# OpenThermEth.net
KiCad netlist of a schematic drawn in EasyEDA Pro
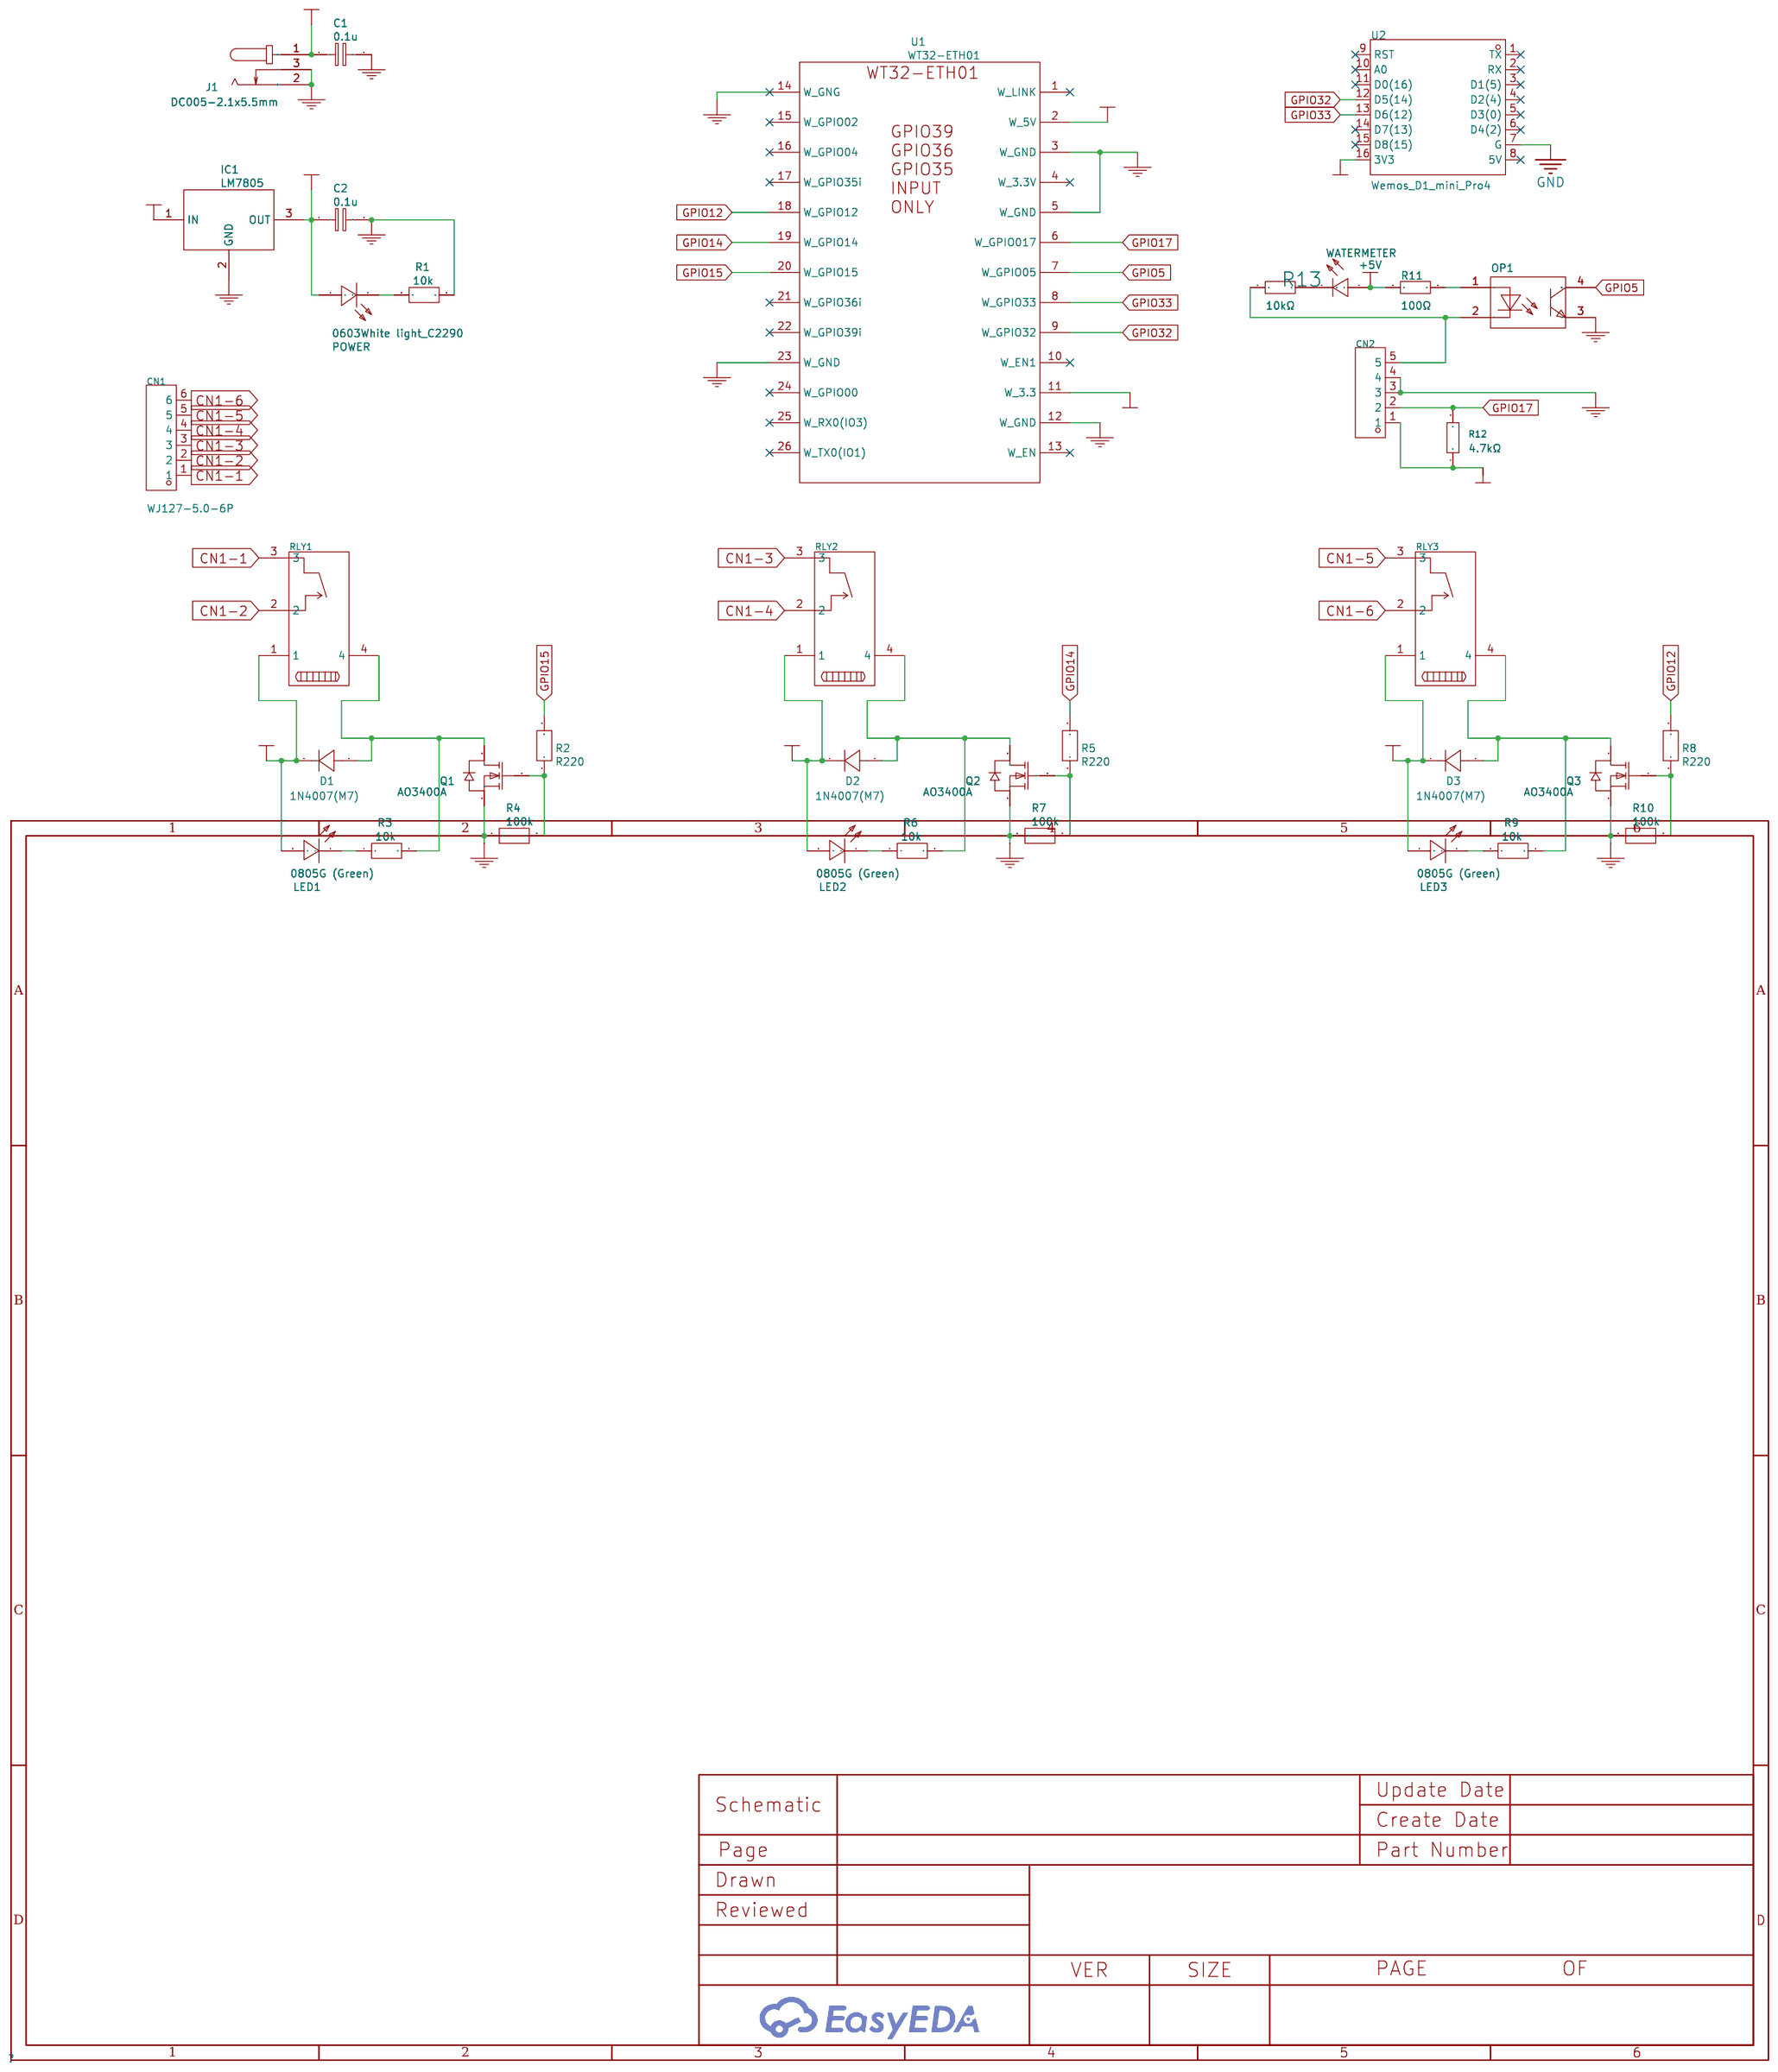
[diagram p0: schematic sheet]

(export (version "E")
  (design (tool "Eeschema 10.0.6"))
  (components
    (comp (ref "C1")
      (value "0.1u")
      (footprint "easyedapro:C0603")
      (fields
        (field (name "Manufacturer Part") "CL05B104KO5NNNC")
        (field (name "Manufacturer") "SAMSUNG(三星)")
      )
      (libsource (lib "easyedapro") (part "0.1u"))
    )
    (comp (ref "C2")
      (value "0.1u")
      (footprint "easyedapro:C0603")
      (fields
        (field (name "Manufacturer Part") "CL05B104KO5NNNC")
        (field (name "Manufacturer") "SAMSUNG(三星)")
      )
      (libsource (lib "easyedapro") (part "0.1u"))
    )
    (comp (ref "CN1")
      (value "WJ127-5.0-6P")
      (footprint "easyedapro:CONN-TH_6P-P5.00_WJ127-5.0-6P")
      (fields (field (name "Manufacturer") "KANGNEX(康奈克斯电气)"))
      (libsource (lib "easyedapro") (part "WJ127-5.0-6P"))
    )
    (comp (ref "CN2")
      (value "WJ127-5.0-5P")
      (footprint "easyedapro:CONN-TH_5P-P5.00_WJ127-5.0-5P")
      (fields (field (name "Manufacturer") "KANGNEX(康奈克斯电气)"))
      (libsource (lib "easyedapro") (part "WJ127-5.0-5P"))
    )
    (comp (ref "D1")
      (value "1N4007(M7)")
      (footprint "easyedapro:SMA_L4.3-W2.7-LS5.1-RD")
      (fields (field (name "Manufacturer") "UMW(友台半导体)"))
      (libsource (lib "easyedapro") (part "1N4007(M7)"))
    )
    (comp (ref "D2")
      (value "1N4007(M7)")
      (footprint "easyedapro:SMA_L4.3-W2.7-LS5.1-RD")
      (fields (field (name "Manufacturer") "UMW(友台半导体)"))
      (libsource (lib "easyedapro") (part "1N4007(M7)"))
    )
    (comp (ref "D3")
      (value "1N4007(M7)")
      (footprint "easyedapro:SMA_L4.3-W2.7-LS5.1-RD")
      (fields (field (name "Manufacturer") "UMW(友台半导体)"))
      (libsource (lib "easyedapro") (part "1N4007(M7)"))
    )
    (comp (ref "IC1")
      (value "LM7805")
      (footprint "easyedapro:LM7805")
      (libsource (lib "easyedapro") (part "LM7805"))
    )
    (comp (ref "J1")
      (value "DC005-2.1x5.5mm")
      (footprint "easyedapro:DC-IN-TH_POWER-JACK")
      (fields (field (name "Manufacturer Part") "POWER-JACK") (field (name "Manufacturer") "索峰"))
      (libsource (lib "easyedapro") (part "DC005-2.1x5.5mm"))
    )
    (comp (ref "LED1")
      (value "0805G (Green)")
      (footprint "easyedapro:LED0805-RD_GREEN")
      (fields (field (name "Manufacturer") "KENTO"))
      (libsource (lib "easyedapro") (part "0805G (Green)"))
    )
    (comp (ref "LED2")
      (value "0805G (Green)")
      (footprint "easyedapro:LED0805-RD_GREEN")
      (fields (field (name "Manufacturer") "KENTO"))
      (libsource (lib "easyedapro") (part "0805G (Green)"))
    )
    (comp (ref "LED3")
      (value "0805G (Green)")
      (footprint "easyedapro:LED0805-RD_GREEN")
      (fields (field (name "Manufacturer") "KENTO"))
      (libsource (lib "easyedapro") (part "0805G (Green)"))
    )
    (comp (ref "OP1")
      (value "EL817S1(C)(TU)-F")
      (footprint "easyedapro:OPTO-SMD-4_L4.6-W6.5-P2.54-LS10.3-TL")
      (fields (field (name "Manufacturer") "EVERLIGHT(亿光)"))
      (libsource (lib "easyedapro") (part "EL817S1(C)(TU)-F"))
    )
    (comp (ref "POWER")
      (value "0603White light_C2290")
      (footprint "easyedapro:LED0603-R-RD_WHITE")
      (fields (field (name "Manufacturer Part") "KT-0603W") (field (name "Manufacturer") "KENTO"))
      (libsource (lib "easyedapro") (part "0603White light_C2290"))
    )
    (comp (ref "Q1")
      (value "AO3400A")
      (footprint "easyedapro:SOT-23-3_L2.9-W1.6-P1.90-LS2.8-BR")
      (fields (field (name "Manufacturer") "AOS"))
      (libsource (lib "easyedapro") (part "AO3400A"))
    )
    (comp (ref "Q2")
      (value "AO3400A")
      (footprint "easyedapro:SOT-23-3_L2.9-W1.6-P1.90-LS2.8-BR")
      (fields (field (name "Manufacturer") "AOS"))
      (libsource (lib "easyedapro") (part "AO3400A"))
    )
    (comp (ref "Q3")
      (value "AO3400A")
      (footprint "easyedapro:SOT-23-3_L2.9-W1.6-P1.90-LS2.8-BR")
      (fields (field (name "Manufacturer") "AOS"))
      (libsource (lib "easyedapro") (part "AO3400A"))
    )
    (comp (ref "R1")
      (value "10k")
      (footprint "easyedapro:R0603")
      (fields
        (field (name "Manufacturer Part") "0603WAF1002T5E")
        (field (name "Manufacturer") "UNI-ROYAL(厚声)")
      )
      (libsource (lib "easyedapro") (part "10k"))
    )
    (comp (ref "R2")
      (value "R220")
      (footprint "easyedapro:R0603")
      (fields
        (field (name "Manufacturer Part") "0603WAF2200T5E")
        (field (name "Manufacturer") "UNI-ROYAL(厚声)")
      )
      (libsource (lib "easyedapro") (part "R220"))
    )
    (comp (ref "R3")
      (value "10k")
      (footprint "easyedapro:R0603")
      (fields
        (field (name "Manufacturer Part") "0603WAF1002T5E")
        (field (name "Manufacturer") "UNI-ROYAL(厚声)")
      )
      (libsource (lib "easyedapro") (part "10k"))
    )
    (comp (ref "R4")
      (value "100k")
      (footprint "easyedapro:R0603")
      (fields
        (field (name "Manufacturer Part") "0603WAF1003T5E")
        (field (name "Manufacturer") "UNI-ROYAL(厚声)")
      )
      (libsource (lib "easyedapro") (part "100k"))
    )
    (comp (ref "R5")
      (value "R220")
      (footprint "easyedapro:R0603")
      (fields
        (field (name "Manufacturer Part") "0603WAF2200T5E")
        (field (name "Manufacturer") "UNI-ROYAL(厚声)")
      )
      (libsource (lib "easyedapro") (part "R220"))
    )
    (comp (ref "R6")
      (value "10k")
      (footprint "easyedapro:R0603")
      (fields
        (field (name "Manufacturer Part") "0603WAF1002T5E")
        (field (name "Manufacturer") "UNI-ROYAL(厚声)")
      )
      (libsource (lib "easyedapro") (part "10k"))
    )
    (comp (ref "R7")
      (value "100k")
      (footprint "easyedapro:R0603")
      (fields
        (field (name "Manufacturer Part") "0603WAF1003T5E")
        (field (name "Manufacturer") "UNI-ROYAL(厚声)")
      )
      (libsource (lib "easyedapro") (part "100k"))
    )
    (comp (ref "R8")
      (value "R220")
      (footprint "easyedapro:R0603")
      (fields
        (field (name "Manufacturer Part") "0603WAF2200T5E")
        (field (name "Manufacturer") "UNI-ROYAL(厚声)")
      )
      (libsource (lib "easyedapro") (part "R220"))
    )
    (comp (ref "R9")
      (value "10k")
      (footprint "easyedapro:R0603")
      (fields
        (field (name "Manufacturer Part") "0603WAF1002T5E")
        (field (name "Manufacturer") "UNI-ROYAL(厚声)")
      )
      (libsource (lib "easyedapro") (part "10k"))
    )
    (comp (ref "R10")
      (value "100k")
      (footprint "easyedapro:R0603")
      (fields
        (field (name "Manufacturer Part") "0603WAF1003T5E")
        (field (name "Manufacturer") "UNI-ROYAL(厚声)")
      )
      (libsource (lib "easyedapro") (part "100k"))
    )
    (comp (ref "R11")
      (value "100Ω")
      (footprint "easyedapro:R0805")
      (fields
        (field (name "Manufacturer Part") "0805W8F1000T5E")
        (field (name "Manufacturer") "UNI-ROYAL(厚声)")
      )
      (libsource (lib "easyedapro") (part "0805W8F1000T5E"))
    )
    (comp (ref "R12")
      (value "4.7kΩ")
      (footprint "easyedapro:R0805")
      (fields
        (field (name "Manufacturer Part") "0805W8F4701T5E")
        (field (name "Manufacturer") "UNI-ROYAL(厚声)")
      )
      (libsource (lib "easyedapro") (part "0805W8F4701T5E"))
    )
    (comp (ref "R13")
      (value "10kΩ")
      (footprint "easyedapro:R0603")
      (fields
        (field (name "Manufacturer Part") "0603WAF1002T5E")
        (field (name "Manufacturer") "UNI-ROYAL(厚声)")
      )
      (libsource (lib "easyedapro") (part "0603WAF1002T5E"))
    )
    (comp (ref "RLY1")
      (value "G5NB-1A-E-DC5V")
      (footprint "easyedapro:RELAY-TH_G5NB-1A-E-DCXX")
      (fields (field (name "Manufacturer") "OMRON(欧姆龙)"))
      (libsource (lib "easyedapro") (part "G5NB-1A-E-DC5V"))
    )
    (comp (ref "RLY2")
      (value "G5NB-1A-E-DC5V")
      (footprint "easyedapro:RELAY-TH_G5NB-1A-E-DCXX")
      (fields (field (name "Manufacturer") "OMRON(欧姆龙)"))
      (libsource (lib "easyedapro") (part "G5NB-1A-E-DC5V"))
    )
    (comp (ref "RLY3")
      (value "G5NB-1A-E-DC5V")
      (footprint "easyedapro:RELAY-TH_G5NB-1A-E-DCXX")
      (fields (field (name "Manufacturer") "OMRON(欧姆龙)"))
      (libsource (lib "easyedapro") (part "G5NB-1A-E-DC5V"))
    )
    (comp (ref "U1")
      (value "WT32-ETH01")
      (footprint "easyedapro:WT32-ETH01-M")
      (fields (field (name "Manufacturer") "Wireless-Tag"))
      (libsource (lib "easyedapro") (part "WT32-ETH01"))
    )
    (comp (ref "U2")
      (value "Wemos_D1_mini_Pro4")
      (footprint "easyedapro:DIP-16_WEMOS_D1_MINI_PRO4")
      (libsource (lib "easyedapro") (part "WEMOS_D1_MINI_PRO4"))
    )
    (comp (ref "WATERMETER")
      (value "19-213/Y2C-CQ2R2L/3T(CY)")
      (footprint "easyedapro:LED0603-RD-YELLOW")
      (fields (field (name "Manufacturer") "EVERLIGHT(亿光)"))
      (libsource (lib "easyedapro") (part "19-213/Y2C-CQ2R2L/3T(CY)"))
    )
  )
  (nets
    (net (code "1") (name "+3.3V") (class "Default")
      (node (ref "CN2") (pin "1") (pinfunction "1_1") (pintype "input"))
      (node (ref "R12") (pin "1") (pinfunction "1_1") (pintype "input"))
      (node (ref "U1") (pin "11") (pinfunction "W_3.3_11") (pintype "unspecified"))
      (node (ref "U2") (pin "16") (pinfunction "3V3_16") (pintype "unspecified"))
    )
    (net (code "2") (name "+5V") (class "Default")
      (node (ref "C2") (pin "1") (pinfunction "1_1") (pintype "unspecified"))
      (node (ref "D1") (pin "1") (pinfunction "K_1") (pintype "unspecified"))
      (node (ref "D2") (pin "1") (pinfunction "K_1") (pintype "unspecified"))
      (node (ref "D3") (pin "1") (pinfunction "K_1") (pintype "unspecified"))
      (node (ref "IC1") (pin "3") (pinfunction "OUT_3") (pintype "unspecified"))
      (node (ref "LED1") (pin "2") (pinfunction "A_2") (pintype "unspecified"))
      (node (ref "LED2") (pin "2") (pinfunction "A_2") (pintype "unspecified"))
      (node (ref "LED3") (pin "2") (pinfunction "A_2") (pintype "unspecified"))
      (node (ref "POWER") (pin "1") (pinfunction "A_1") (pintype "unspecified"))
      (node (ref "R11") (pin "1") (pinfunction "1_1") (pintype "input"))
      (node (ref "RLY1") (pin "1") (pinfunction "1_1") (pintype "input"))
      (node (ref "RLY2") (pin "1") (pinfunction "1_1") (pintype "input"))
      (node (ref "RLY3") (pin "1") (pinfunction "1_1") (pintype "input"))
      (node (ref "U1") (pin "2") (pinfunction "W_5V_2") (pintype "unspecified"))
      (node (ref "WATERMETER") (pin "2") (pinfunction "A_2") (pintype "input"))
    )
    (net (code "3") (name "CN1-1") (class "Default")
      (node (ref "CN1") (pin "1") (pinfunction "1_1") (pintype "input"))
      (node (ref "RLY1") (pin "3") (pinfunction "3_3") (pintype "input"))
    )
    (net (code "4") (name "CN1-2") (class "Default")
      (node (ref "CN1") (pin "2") (pinfunction "2_2") (pintype "input"))
      (node (ref "RLY1") (pin "2") (pinfunction "2_2") (pintype "input"))
    )
    (net (code "5") (name "CN1-3") (class "Default")
      (node (ref "CN1") (pin "3") (pinfunction "3_3") (pintype "input"))
      (node (ref "RLY2") (pin "3") (pinfunction "3_3") (pintype "input"))
    )
    (net (code "6") (name "CN1-4") (class "Default")
      (node (ref "CN1") (pin "4") (pinfunction "4_4") (pintype "input"))
      (node (ref "RLY2") (pin "2") (pinfunction "2_2") (pintype "input"))
    )
    (net (code "7") (name "CN1-5") (class "Default")
      (node (ref "CN1") (pin "5") (pinfunction "5_5") (pintype "input"))
      (node (ref "RLY3") (pin "3") (pinfunction "3_3") (pintype "input"))
    )
    (net (code "8") (name "CN1-6") (class "Default")
      (node (ref "CN1") (pin "6") (pinfunction "6_6") (pintype "input"))
      (node (ref "RLY3") (pin "2") (pinfunction "2_2") (pintype "input"))
    )
    (net (code "9") (name "GND") (class "Default")
      (node (ref "C1") (pin "2") (pinfunction "2_2") (pintype "unspecified"))
      (node (ref "C2") (pin "2") (pinfunction "2_2") (pintype "unspecified"))
      (node (ref "CN2") (pin "3") (pinfunction "3_3") (pintype "input"))
      (node (ref "CN2") (pin "4") (pinfunction "4_4") (pintype "input"))
      (node (ref "IC1") (pin "2") (pinfunction "GND_2") (pintype "unspecified"))
      (node (ref "J1") (pin "2") (pinfunction "GND_2") (pintype "unspecified"))
      (node (ref "J1") (pin "3") (pinfunction "3_3") (pintype "unspecified"))
      (node (ref "OP1") (pin "3") (pinfunction "EM_3") (pintype "unspecified"))
      (node (ref "Q1") (pin "2") (pinfunction "S_2") (pintype "unspecified"))
      (node (ref "Q2") (pin "2") (pinfunction "S_2") (pintype "unspecified"))
      (node (ref "Q3") (pin "2") (pinfunction "S_2") (pintype "unspecified"))
      (node (ref "R1") (pin "2") (pinfunction "2_2") (pintype "unspecified"))
      (node (ref "R10") (pin "1") (pinfunction "1_1") (pintype "unspecified"))
      (node (ref "R4") (pin "1") (pinfunction "1_1") (pintype "unspecified"))
      (node (ref "R7") (pin "1") (pinfunction "1_1") (pintype "unspecified"))
      (node (ref "U1") (pin "12") (pinfunction "W_GND_12") (pintype "unspecified"))
      (node (ref "U1") (pin "14") (pinfunction "W_GNG_14") (pintype "unspecified"))
      (node (ref "U1") (pin "23") (pinfunction "W_GND_23") (pintype "unspecified"))
      (node (ref "U1") (pin "3") (pinfunction "W_GND_3") (pintype "unspecified"))
      (node (ref "U1") (pin "5") (pinfunction "W_GND_5") (pintype "unspecified"))
      (node (ref "U2") (pin "7") (pinfunction "G_7") (pintype "unspecified"))
    )
    (net (code "10") (name "GPIO5") (class "Default")
      (node (ref "OP1") (pin "4") (pinfunction "COL_4") (pintype "unspecified"))
      (node (ref "U1") (pin "7") (pinfunction "W_GPIO05_7") (pintype "unspecified"))
    )
    (net (code "11") (name "GPIO12") (class "Default")
      (node (ref "R8") (pin "2") (pinfunction "2_2") (pintype "unspecified"))
      (node (ref "U1") (pin "18") (pinfunction "W_GPIO12_18") (pintype "unspecified"))
    )
    (net (code "12") (name "GPIO14") (class "Default")
      (node (ref "R5") (pin "2") (pinfunction "2_2") (pintype "unspecified"))
      (node (ref "U1") (pin "19") (pinfunction "W_GPIO14_19") (pintype "unspecified"))
    )
    (net (code "13") (name "GPIO15") (class "Default")
      (node (ref "R2") (pin "2") (pinfunction "2_2") (pintype "unspecified"))
      (node (ref "U1") (pin "20") (pinfunction "W_GPIO15_20") (pintype "unspecified"))
    )
    (net (code "14") (name "GPIO17") (class "Default")
      (node (ref "CN2") (pin "2") (pinfunction "2_2") (pintype "input"))
      (node (ref "R12") (pin "2") (pinfunction "2_2") (pintype "input"))
      (node (ref "U1") (pin "6") (pinfunction "W_GPIO017_6") (pintype "unspecified"))
    )
    (net (code "15") (name "GPIO32") (class "Default")
      (node (ref "U1") (pin "9") (pinfunction "W_GPIO32_9") (pintype "unspecified"))
      (node (ref "U2") (pin "12") (pinfunction "D5(14)_12") (pintype "unspecified"))
    )
    (net (code "16") (name "GPIO33") (class "Default")
      (node (ref "U1") (pin "8") (pinfunction "W_GPIO33_8") (pintype "unspecified"))
      (node (ref "U2") (pin "13") (pinfunction "D6(12)_13") (pintype "unspecified"))
    )
    (net (code "17") (name "Net-(D1-A)") (class "Default")
      (node (ref "D1") (pin "2") (pinfunction "A_2") (pintype "unspecified"))
      (node (ref "Q1") (pin "3") (pinfunction "D_3") (pintype "unspecified"))
      (node (ref "R3") (pin "2") (pinfunction "2_2") (pintype "unspecified"))
      (node (ref "RLY1") (pin "4") (pinfunction "4_4") (pintype "input"))
    )
    (net (code "18") (name "Net-(D2-A)") (class "Default")
      (node (ref "D2") (pin "2") (pinfunction "A_2") (pintype "unspecified"))
      (node (ref "Q2") (pin "3") (pinfunction "D_3") (pintype "unspecified"))
      (node (ref "R6") (pin "2") (pinfunction "2_2") (pintype "unspecified"))
      (node (ref "RLY2") (pin "4") (pinfunction "4_4") (pintype "input"))
    )
    (net (code "19") (name "Net-(D3-A)") (class "Default")
      (node (ref "D3") (pin "2") (pinfunction "A_2") (pintype "unspecified"))
      (node (ref "Q3") (pin "3") (pinfunction "D_3") (pintype "unspecified"))
      (node (ref "R9") (pin "2") (pinfunction "2_2") (pintype "unspecified"))
      (node (ref "RLY3") (pin "4") (pinfunction "4_4") (pintype "input"))
    )
    (net (code "20") (name "Net-(LED1-K)") (class "Default")
      (node (ref "LED1") (pin "1") (pinfunction "K_1") (pintype "unspecified"))
      (node (ref "R3") (pin "1") (pinfunction "1_1") (pintype "unspecified"))
    )
    (net (code "21") (name "Net-(LED2-K)") (class "Default")
      (node (ref "LED2") (pin "1") (pinfunction "K_1") (pintype "unspecified"))
      (node (ref "R6") (pin "1") (pinfunction "1_1") (pintype "unspecified"))
    )
    (net (code "22") (name "Net-(LED3-K)") (class "Default")
      (node (ref "LED3") (pin "1") (pinfunction "K_1") (pintype "unspecified"))
      (node (ref "R9") (pin "1") (pinfunction "1_1") (pintype "unspecified"))
    )
    (net (code "23") (name "Net-(OP1-AN)") (class "Default")
      (node (ref "OP1") (pin "1") (pinfunction "AN_1") (pintype "unspecified"))
      (node (ref "R11") (pin "2") (pinfunction "2_2") (pintype "input"))
    )
    (net (code "24") (name "Net-(OP1-CAT)") (class "Default")
      (node (ref "CN2") (pin "5") (pinfunction "5_5") (pintype "input"))
      (node (ref "OP1") (pin "2") (pinfunction "CAT_2") (pintype "unspecified"))
      (node (ref "R13") (pin "1") (pinfunction "1_1") (pintype "input"))
    )
    (net (code "25") (name "Net-(POWER-K)") (class "Default")
      (node (ref "POWER") (pin "2") (pinfunction "K_2") (pintype "unspecified"))
      (node (ref "R1") (pin "1") (pinfunction "1_1") (pintype "unspecified"))
    )
    (net (code "26") (name "Net-(Q1-G)") (class "Default")
      (node (ref "Q1") (pin "1") (pinfunction "G_1") (pintype "unspecified"))
      (node (ref "R2") (pin "1") (pinfunction "1_1") (pintype "unspecified"))
      (node (ref "R4") (pin "2") (pinfunction "2_2") (pintype "unspecified"))
    )
    (net (code "27") (name "Net-(Q2-G)") (class "Default")
      (node (ref "Q2") (pin "1") (pinfunction "G_1") (pintype "unspecified"))
      (node (ref "R5") (pin "1") (pinfunction "1_1") (pintype "unspecified"))
      (node (ref "R7") (pin "2") (pinfunction "2_2") (pintype "unspecified"))
    )
    (net (code "28") (name "Net-(Q3-G)") (class "Default")
      (node (ref "Q3") (pin "1") (pinfunction "G_1") (pintype "unspecified"))
      (node (ref "R10") (pin "2") (pinfunction "2_2") (pintype "unspecified"))
      (node (ref "R8") (pin "1") (pinfunction "1_1") (pintype "unspecified"))
    )
    (net (code "29") (name "Net-(WATERMETER-C)") (class "Default")
      (node (ref "R13") (pin "2") (pinfunction "2_2") (pintype "input"))
      (node (ref "WATERMETER") (pin "1") (pinfunction "C_1") (pintype "input"))
    )
    (net (code "30") (name "VCC") (class "Default")
      (node (ref "C1") (pin "1") (pinfunction "1_1") (pintype "unspecified"))
      (node (ref "IC1") (pin "1") (pinfunction "IN_1") (pintype "unspecified"))
      (node (ref "J1") (pin "1") (pinfunction "VCC_1") (pintype "unspecified"))
    )
    (net (code "31") (name "unconnected-(U1-W_3.3V-Pad4)") (class "Default")
      (node (ref "U1") (pin "4") (pinfunction "W_3.3V_4") (pintype "unspecified+no_connect"))
    )
    (net (code "32") (name "unconnected-(U1-W_EN-Pad13)") (class "Default")
      (node (ref "U1") (pin "13") (pinfunction "W_EN_13") (pintype "unspecified+no_connect"))
    )
    (net (code "33") (name "unconnected-(U1-W_EN1-Pad10)") (class "Default")
      (node (ref "U1") (pin "10") (pinfunction "W_EN1_10") (pintype "unspecified+no_connect"))
    )
    (net (code "34") (name "unconnected-(U1-W_GPIO00-Pad24)") (class "Default")
      (node (ref "U1") (pin "24") (pinfunction "W_GPIO00_24") (pintype "unspecified+no_connect"))
    )
    (net (code "35") (name "unconnected-(U1-W_GPIO02-Pad15)") (class "Default")
      (node (ref "U1") (pin "15") (pinfunction "W_GPIO02_15") (pintype "unspecified+no_connect"))
    )
    (net (code "36") (name "unconnected-(U1-W_GPIO04-Pad16)") (class "Default")
      (node (ref "U1") (pin "16") (pinfunction "W_GPIO04_16") (pintype "unspecified+no_connect"))
    )
    (net (code "37") (name "unconnected-(U1-W_GPIO35i-Pad17)") (class "Default")
      (node (ref "U1") (pin "17") (pinfunction "W_GPIO35i_17") (pintype "unspecified+no_connect"))
    )
    (net (code "38") (name "unconnected-(U1-W_GPIO36i-Pad21)") (class "Default")
      (node (ref "U1") (pin "21") (pinfunction "W_GPIO36i_21") (pintype "unspecified+no_connect"))
    )
    (net (code "39") (name "unconnected-(U1-W_GPIO39i-Pad22)") (class "Default")
      (node (ref "U1") (pin "22") (pinfunction "W_GPIO39i_22") (pintype "unspecified+no_connect"))
    )
    (net (code "40") (name "unconnected-(U1-W_LINK-Pad1)") (class "Default")
      (node (ref "U1") (pin "1") (pinfunction "W_LINK_1") (pintype "unspecified+no_connect"))
    )
    (net (code "41") (name "unconnected-(U1-W_RX0(IO3)-Pad25)") (class "Default")
      (node (ref "U1") (pin "25") (pinfunction "W_RX0(IO3)_25") (pintype "unspecified+no_connect"))
    )
    (net (code "42") (name "unconnected-(U1-W_TX0(IO1)-Pad26)") (class "Default")
      (node (ref "U1") (pin "26") (pinfunction "W_TX0(IO1)_26") (pintype "unspecified+no_connect"))
    )
    (net (code "43") (name "unconnected-(U2-5V-Pad8)") (class "Default")
      (node (ref "U2") (pin "8") (pinfunction "5V_8") (pintype "unspecified+no_connect"))
    )
    (net (code "44") (name "unconnected-(U2-A0-Pad10)") (class "Default")
      (node (ref "U2") (pin "10") (pinfunction "A0_10") (pintype "unspecified+no_connect"))
    )
    (net (code "45") (name "unconnected-(U2-D0(16)-Pad11)") (class "Default")
      (node (ref "U2") (pin "11") (pinfunction "D0(16)_11") (pintype "unspecified+no_connect"))
    )
    (net (code "46") (name "unconnected-(U2-D1(5)-Pad3)") (class "Default")
      (node (ref "U2") (pin "3") (pinfunction "D1(5)_3") (pintype "unspecified+no_connect"))
    )
    (net (code "47") (name "unconnected-(U2-D2(4)-Pad4)") (class "Default")
      (node (ref "U2") (pin "4") (pinfunction "D2(4)_4") (pintype "unspecified+no_connect"))
    )
    (net (code "48") (name "unconnected-(U2-D3(0)-Pad5)") (class "Default")
      (node (ref "U2") (pin "5") (pinfunction "D3(0)_5") (pintype "unspecified+no_connect"))
    )
    (net (code "49") (name "unconnected-(U2-D4(2)-Pad6)") (class "Default")
      (node (ref "U2") (pin "6") (pinfunction "D4(2)_6") (pintype "unspecified+no_connect"))
    )
    (net (code "50") (name "unconnected-(U2-D7(13)-Pad14)") (class "Default")
      (node (ref "U2") (pin "14") (pinfunction "D7(13)_14") (pintype "unspecified+no_connect"))
    )
    (net (code "51") (name "unconnected-(U2-D8(15)-Pad15)") (class "Default")
      (node (ref "U2") (pin "15") (pinfunction "D8(15)_15") (pintype "unspecified+no_connect"))
    )
    (net (code "52") (name "unconnected-(U2-RST-Pad9)") (class "Default")
      (node (ref "U2") (pin "9") (pinfunction "RST_9") (pintype "unspecified+no_connect"))
    )
    (net (code "53") (name "unconnected-(U2-RX-Pad2)") (class "Default")
      (node (ref "U2") (pin "2") (pinfunction "RX_2") (pintype "unspecified+no_connect"))
    )
    (net (code "54") (name "unconnected-(U2-TX-Pad1)") (class "Default")
      (node (ref "U2") (pin "1") (pinfunction "TX_1") (pintype "unspecified+no_connect"))
    )
  )
)
